# HackAJeep3.net
KiCad netlist of a schematic drawn in EAGLE
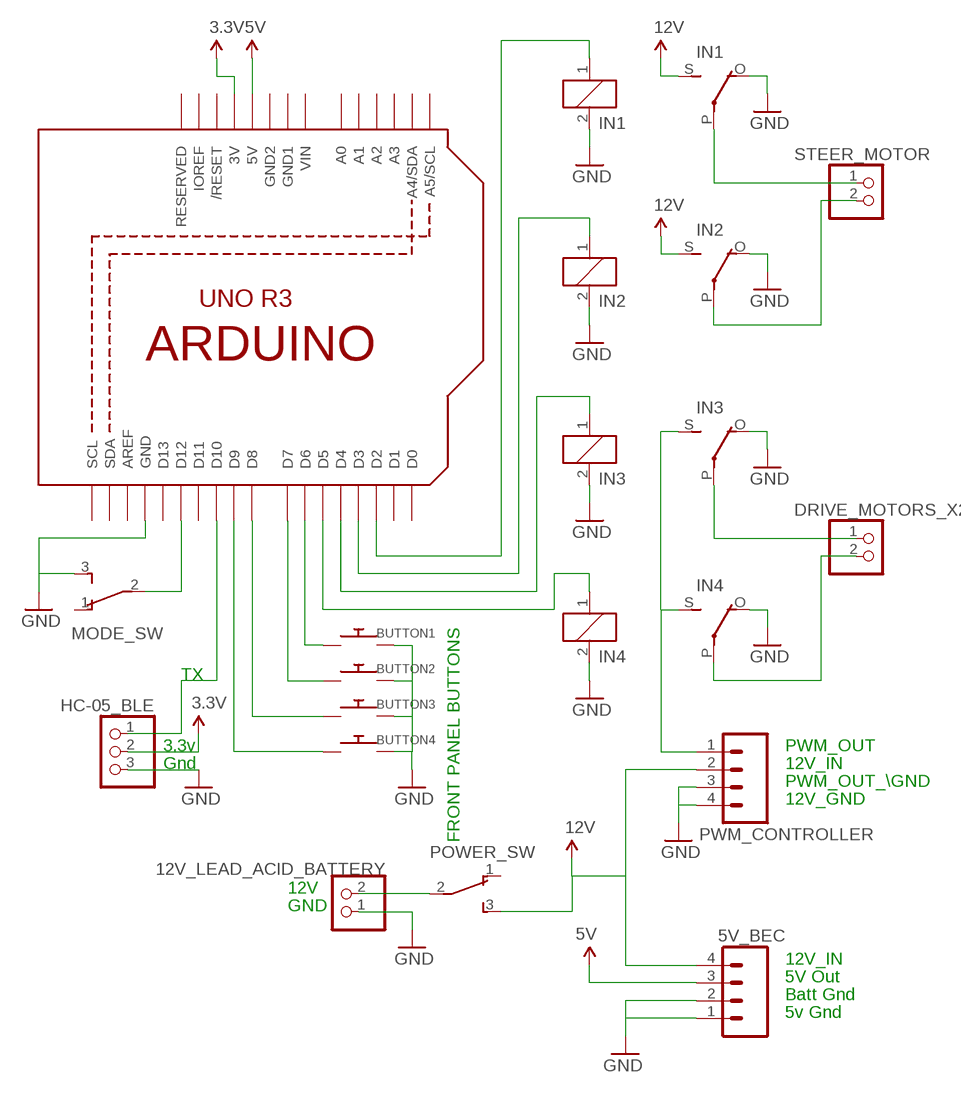
[diagram p0: schematic, sheet 1]

(export (version "E")
  (design (tool "Eeschema 10.0.6"))
  (components
    (comp (ref "5V_BEC")
      (value "M04POLAR")
      (footprint "eagle-import:MOLEX-1X4")
      (libsource (lib "eagle-import") (part "M04POLAR"))
    )
    (comp (ref "12V_LEAD_ACID_BATTERY")
      (value "PINHD-1X2")
      (footprint "eagle-import:1X02")
      (libsource (lib "eagle-import") (part "PINHD-1X2"))
    )
    (comp (ref "BUTTON1")
      (value "SWITCH_PUSHBUTTONSOFTTOUCHSMD_SJ")
      (footprint "eagle-import:PUSHBUTTON_SMD_SJ")
      (libsource (lib "eagle-import") (part "SWITCH_PUSHBUTTONSOFTTOUCHSMD_SJ"))
    )
    (comp (ref "BUTTON2")
      (value "SWITCH_PUSHBUTTONSOFTTOUCHSMD_SJ")
      (footprint "eagle-import:PUSHBUTTON_SMD_SJ")
      (libsource (lib "eagle-import") (part "SWITCH_PUSHBUTTONSOFTTOUCHSMD_SJ"))
    )
    (comp (ref "BUTTON3")
      (value "SWITCH_PUSHBUTTONSOFTTOUCHSMD_SJ")
      (footprint "eagle-import:PUSHBUTTON_SMD_SJ")
      (libsource (lib "eagle-import") (part "SWITCH_PUSHBUTTONSOFTTOUCHSMD_SJ"))
    )
    (comp (ref "BUTTON4")
      (value "SWITCH_PUSHBUTTONSOFTTOUCHSMD_SJ")
      (footprint "eagle-import:PUSHBUTTON_SMD_SJ")
      (libsource (lib "eagle-import") (part "SWITCH_PUSHBUTTONSOFTTOUCHSMD_SJ"))
    )
    (comp (ref "DRIVE_MOTORS_X2")
      (value "PINHD-1X2")
      (footprint "eagle-import:1X02")
      (libsource (lib "eagle-import") (part "PINHD-1X2"))
    )
    (comp (ref "HC-05_BLE")
      (value "PINHD-1X3")
      (footprint "eagle-import:1X03")
      (libsource (lib "eagle-import") (part "PINHD-1X3"))
    )
    (comp (ref "IN1")
      (value "E3206L")
      (footprint "eagle-import:E3206L")
      (libsource (lib "eagle-import") (part "E3206L"))
    )
    (comp (ref "IN2")
      (value "E3206L")
      (footprint "eagle-import:E3206L")
      (libsource (lib "eagle-import") (part "E3206L"))
    )
    (comp (ref "IN3")
      (value "E3206L")
      (footprint "eagle-import:E3206L")
      (libsource (lib "eagle-import") (part "E3206L"))
    )
    (comp (ref "IN4")
      (value "E3206L")
      (footprint "eagle-import:E3206L")
      (libsource (lib "eagle-import") (part "E3206L"))
    )
    (comp (ref "MODE_SW")
      (value "TL36WO")
      (footprint "eagle-import:TL3XWO")
      (libsource (lib "eagle-import") (part "TL36WO"))
    )
    (comp (ref "POWER_SW")
      (value "TL36WO")
      (footprint "eagle-import:TL3XWO")
      (libsource (lib "eagle-import") (part "TL36WO"))
    )
    (comp (ref "PWM_CONTROLLER")
      (value "M04POLAR")
      (footprint "eagle-import:MOLEX-1X4")
      (libsource (lib "eagle-import") (part "M04POLAR"))
    )
    (comp (ref "STEER_MOTOR")
      (value "PINHD-1X2")
      (footprint "eagle-import:1X02")
      (libsource (lib "eagle-import") (part "PINHD-1X2"))
    )
    (comp (ref "U1")
      (value "ARDUINOR3-DIMENSION")
      (footprint "eagle-import:ARDUINOR3")
      (libsource (lib "eagle-import") (part "ARDUINOR3-DIMENSION"))
    )
  )
  (nets
    (net (code "1") (name "/GND1") (class "Default")
      (node (ref "U1") (pin "GND1") (pinfunction "GND1_GND1") (pintype "power_in"))
    )
    (net (code "2") (name "/GND2") (class "Default")
      (node (ref "U1") (pin "GND2") (pinfunction "GND2_GND2") (pintype "power_in"))
    )
    (net (code "3") (name "/VIN") (class "Default")
      (node (ref "U1") (pin "VIN") (pinfunction "VIN_VIN") (pintype "power_in"))
    )
    (net (code "4") (name "3.3V") (class "Default")
      (node (ref "HC-05_BLE") (pin "2") (pinfunction "2_2") (pintype "passive"))
      (node (ref "U1") (pin "3V") (pinfunction "3V_3V") (pintype "power_in"))
    )
    (net (code "5") (name "5V") (class "Default")
      (node (ref "5V_BEC") (pin "3") (pinfunction "3_3") (pintype "passive"))
      (node (ref "U1") (pin "5V") (pinfunction "5V_5V") (pintype "power_in"))
    )
    (net (code "6") (name "12V") (class "Default")
      (node (ref "5V_BEC") (pin "4") (pinfunction "4_4") (pintype "passive"))
      (node (ref "IN1") (pin "S") (pinfunction "S_S") (pintype "passive"))
      (node (ref "IN2") (pin "S") (pinfunction "S_S") (pintype "passive"))
      (node (ref "POWER_SW") (pin "3") (pinfunction "S_3") (pintype "passive"))
      (node (ref "PWM_CONTROLLER") (pin "2") (pinfunction "2_2") (pintype "passive"))
    )
    (net (code "7") (name "GND") (class "Default")
      (node (ref "12V_LEAD_ACID_BATTERY") (pin "1") (pinfunction "1_1") (pintype "passive"))
      (node (ref "5V_BEC") (pin "1") (pinfunction "1_1") (pintype "passive"))
      (node (ref "5V_BEC") (pin "2") (pinfunction "2_2") (pintype "passive"))
      (node (ref "BUTTON1") (pin "P$2") (pinfunction "P$2_P$2") (pintype "passive"))
      (node (ref "BUTTON2") (pin "P$2") (pinfunction "P$2_P$2") (pintype "passive"))
      (node (ref "BUTTON3") (pin "P$2") (pinfunction "P$2_P$2") (pintype "passive"))
      (node (ref "BUTTON4") (pin "P$2") (pinfunction "P$2_P$2") (pintype "passive"))
      (node (ref "HC-05_BLE") (pin "3") (pinfunction "3_3") (pintype "passive"))
      (node (ref "IN1") (pin "2") (pinfunction "2_2") (pintype "passive"))
      (node (ref "IN1") (pin "O") (pinfunction "O_O") (pintype "passive"))
      (node (ref "IN2") (pin "2") (pinfunction "2_2") (pintype "passive"))
      (node (ref "IN2") (pin "O") (pinfunction "O_O") (pintype "passive"))
      (node (ref "IN3") (pin "2") (pinfunction "2_2") (pintype "passive"))
      (node (ref "IN3") (pin "O") (pinfunction "O_O") (pintype "passive"))
      (node (ref "IN4") (pin "2") (pinfunction "2_2") (pintype "passive"))
      (node (ref "IN4") (pin "O") (pinfunction "O_O") (pintype "passive"))
      (node (ref "MODE_SW") (pin "3") (pinfunction "S_3") (pintype "passive"))
      (node (ref "PWM_CONTROLLER") (pin "3") (pinfunction "3_3") (pintype "passive"))
      (node (ref "PWM_CONTROLLER") (pin "4") (pinfunction "4_4") (pintype "passive"))
      (node (ref "U1") (pin "GND") (pinfunction "GND_GND") (pintype "power_in"))
    )
    (net (code "8") (name "Net-(BUTTON1-PadP$1)") (class "Default")
      (node (ref "BUTTON1") (pin "P$1") (pinfunction "P$1_P$1") (pintype "passive"))
      (node (ref "U1") (pin "D6") (pinfunction "D6_D6") (pintype "bidirectional"))
    )
    (net (code "9") (name "Net-(BUTTON2-PadP$1)") (class "Default")
      (node (ref "BUTTON2") (pin "P$1") (pinfunction "P$1_P$1") (pintype "passive"))
      (node (ref "U1") (pin "D7") (pinfunction "D7_D7") (pintype "bidirectional"))
    )
    (net (code "10") (name "Net-(BUTTON3-PadP$1)") (class "Default")
      (node (ref "BUTTON3") (pin "P$1") (pinfunction "P$1_P$1") (pintype "passive"))
      (node (ref "U1") (pin "D8") (pinfunction "D8_D8") (pintype "bidirectional"))
    )
    (net (code "11") (name "Net-(BUTTON4-PadP$1)") (class "Default")
      (node (ref "BUTTON4") (pin "P$1") (pinfunction "P$1_P$1") (pintype "passive"))
      (node (ref "U1") (pin "D9") (pinfunction "D9_D9") (pintype "bidirectional"))
    )
    (net (code "12") (name "Net-(DRIVE_MOTORS_X2-Pad1)") (class "Default")
      (node (ref "DRIVE_MOTORS_X2") (pin "1") (pinfunction "1_1") (pintype "passive"))
      (node (ref "IN3") (pin "P") (pinfunction "P_P") (pintype "passive"))
    )
    (net (code "13") (name "Net-(DRIVE_MOTORS_X2-Pad2)") (class "Default")
      (node (ref "DRIVE_MOTORS_X2") (pin "2") (pinfunction "2_2") (pintype "passive"))
      (node (ref "IN4") (pin "P") (pinfunction "P_P") (pintype "passive"))
    )
    (net (code "14") (name "Net-(HC-05_BLE-Pad1)") (class "Default")
      (node (ref "HC-05_BLE") (pin "1") (pinfunction "1_1") (pintype "passive"))
      (node (ref "U1") (pin "D10") (pinfunction "D10_D10") (pintype "bidirectional"))
    )
    (net (code "15") (name "Net-(IN1-Pad1)") (class "Default")
      (node (ref "IN1") (pin "1") (pinfunction "1_1") (pintype "passive"))
      (node (ref "U1") (pin "D2") (pinfunction "D2_D2") (pintype "bidirectional"))
    )
    (net (code "16") (name "Net-(IN1-PadP)") (class "Default")
      (node (ref "IN1") (pin "P") (pinfunction "P_P") (pintype "passive"))
      (node (ref "STEER_MOTOR") (pin "1") (pinfunction "1_1") (pintype "passive"))
    )
    (net (code "17") (name "Net-(IN2-Pad1)") (class "Default")
      (node (ref "IN2") (pin "1") (pinfunction "1_1") (pintype "passive"))
      (node (ref "U1") (pin "D3") (pinfunction "D3_D3") (pintype "bidirectional"))
    )
    (net (code "18") (name "Net-(IN2-PadP)") (class "Default")
      (node (ref "IN2") (pin "P") (pinfunction "P_P") (pintype "passive"))
      (node (ref "STEER_MOTOR") (pin "2") (pinfunction "2_2") (pintype "passive"))
    )
    (net (code "19") (name "Net-(IN3-Pad1)") (class "Default")
      (node (ref "IN3") (pin "1") (pinfunction "1_1") (pintype "passive"))
      (node (ref "U1") (pin "D4") (pinfunction "D4_D4") (pintype "bidirectional"))
    )
    (net (code "20") (name "Net-(IN3-PadS)") (class "Default")
      (node (ref "IN3") (pin "S") (pinfunction "S_S") (pintype "passive"))
      (node (ref "IN4") (pin "S") (pinfunction "S_S") (pintype "passive"))
      (node (ref "PWM_CONTROLLER") (pin "1") (pinfunction "1_1") (pintype "passive"))
    )
    (net (code "21") (name "Net-(IN4-Pad1)") (class "Default")
      (node (ref "IN4") (pin "1") (pinfunction "1_1") (pintype "passive"))
      (node (ref "U1") (pin "D5") (pinfunction "D5_D5") (pintype "bidirectional"))
    )
    (net (code "22") (name "Net-(MODE_SW-P)") (class "Default")
      (node (ref "MODE_SW") (pin "2") (pinfunction "P_2") (pintype "passive"))
      (node (ref "U1") (pin "D12") (pinfunction "D12_D12") (pintype "bidirectional"))
    )
    (net (code "23") (name "Net-(POWER_SW-P)") (class "Default")
      (node (ref "12V_LEAD_ACID_BATTERY") (pin "2") (pinfunction "2_2") (pintype "passive"))
      (node (ref "POWER_SW") (pin "2") (pinfunction "P_2") (pintype "passive"))
    )
    (net (code "24") (name "unconnected-(MODE_SW-O-Pad1)") (class "Default")
      (node (ref "MODE_SW") (pin "1") (pinfunction "O_1") (pintype "passive"))
    )
    (net (code "25") (name "unconnected-(POWER_SW-O-Pad1)") (class "Default")
      (node (ref "POWER_SW") (pin "1") (pinfunction "O_1") (pintype "passive"))
    )
    (net (code "26") (name "unconnected-(U1-A4{slash}SDA-PadA4)") (class "Default")
      (node (ref "U1") (pin "A4") (pinfunction "A4/SDA_A4") (pintype "bidirectional"))
    )
    (net (code "27") (name "unconnected-(U1-A5{slash}SCL-PadA5)") (class "Default")
      (node (ref "U1") (pin "A5") (pinfunction "A5/SCL_A5") (pintype "bidirectional"))
    )
    (net (code "28") (name "unconnected-(U1-PadA0)") (class "Default")
      (node (ref "U1") (pin "A0") (pinfunction "A0_A0") (pintype "bidirectional"))
    )
    (net (code "29") (name "unconnected-(U1-PadA1)") (class "Default")
      (node (ref "U1") (pin "A1") (pinfunction "A1_A1") (pintype "bidirectional"))
    )
    (net (code "30") (name "unconnected-(U1-PadA2)") (class "Default")
      (node (ref "U1") (pin "A2") (pinfunction "A2_A2") (pintype "bidirectional"))
    )
    (net (code "31") (name "unconnected-(U1-PadA3)") (class "Default")
      (node (ref "U1") (pin "A3") (pinfunction "A3_A3") (pintype "bidirectional"))
    )
    (net (code "32") (name "unconnected-(U1-PadAREF)") (class "Default")
      (node (ref "U1") (pin "AREF") (pinfunction "AREF_AREF") (pintype "bidirectional"))
    )
    (net (code "33") (name "unconnected-(U1-PadD0)") (class "Default")
      (node (ref "U1") (pin "D0") (pinfunction "D0_D0") (pintype "bidirectional"))
    )
    (net (code "34") (name "unconnected-(U1-PadD1)") (class "Default")
      (node (ref "U1") (pin "D1") (pinfunction "D1_D1") (pintype "bidirectional"))
    )
    (net (code "35") (name "unconnected-(U1-PadD11)") (class "Default")
      (node (ref "U1") (pin "D11") (pinfunction "D11_D11") (pintype "bidirectional"))
    )
    (net (code "36") (name "unconnected-(U1-PadD13)") (class "Default")
      (node (ref "U1") (pin "D13") (pinfunction "D13_D13") (pintype "bidirectional"))
    )
    (net (code "37") (name "unconnected-(U1-PadIOREF)") (class "Default")
      (node (ref "U1") (pin "IOREF") (pinfunction "IOREF_IOREF") (pintype "output"))
    )
    (net (code "38") (name "unconnected-(U1-PadRESERVED)") (class "Default")
      (node (ref "U1") (pin "RESERVED") (pinfunction "RESERVED_RESERVED") (pintype "no_connect"))
    )
    (net (code "39") (name "unconnected-(U1-PadSCL)") (class "Default")
      (node (ref "U1") (pin "SCL") (pinfunction "SCL_SCL") (pintype "bidirectional"))
    )
    (net (code "40") (name "unconnected-(U1-PadSDA)") (class "Default")
      (node (ref "U1") (pin "SDA") (pinfunction "SDA_SDA") (pintype "bidirectional"))
    )
    (net (code "41") (name "unconnected-(U1-{slash}RESET-PadRESET)") (class "Default")
      (node (ref "U1") (pin "RESET") (pinfunction "/RESET_RESET") (pintype "bidirectional"))
    )
  )
)
